# Power_Supply.net
KiCad netlist of a schematic drawn in EAGLE
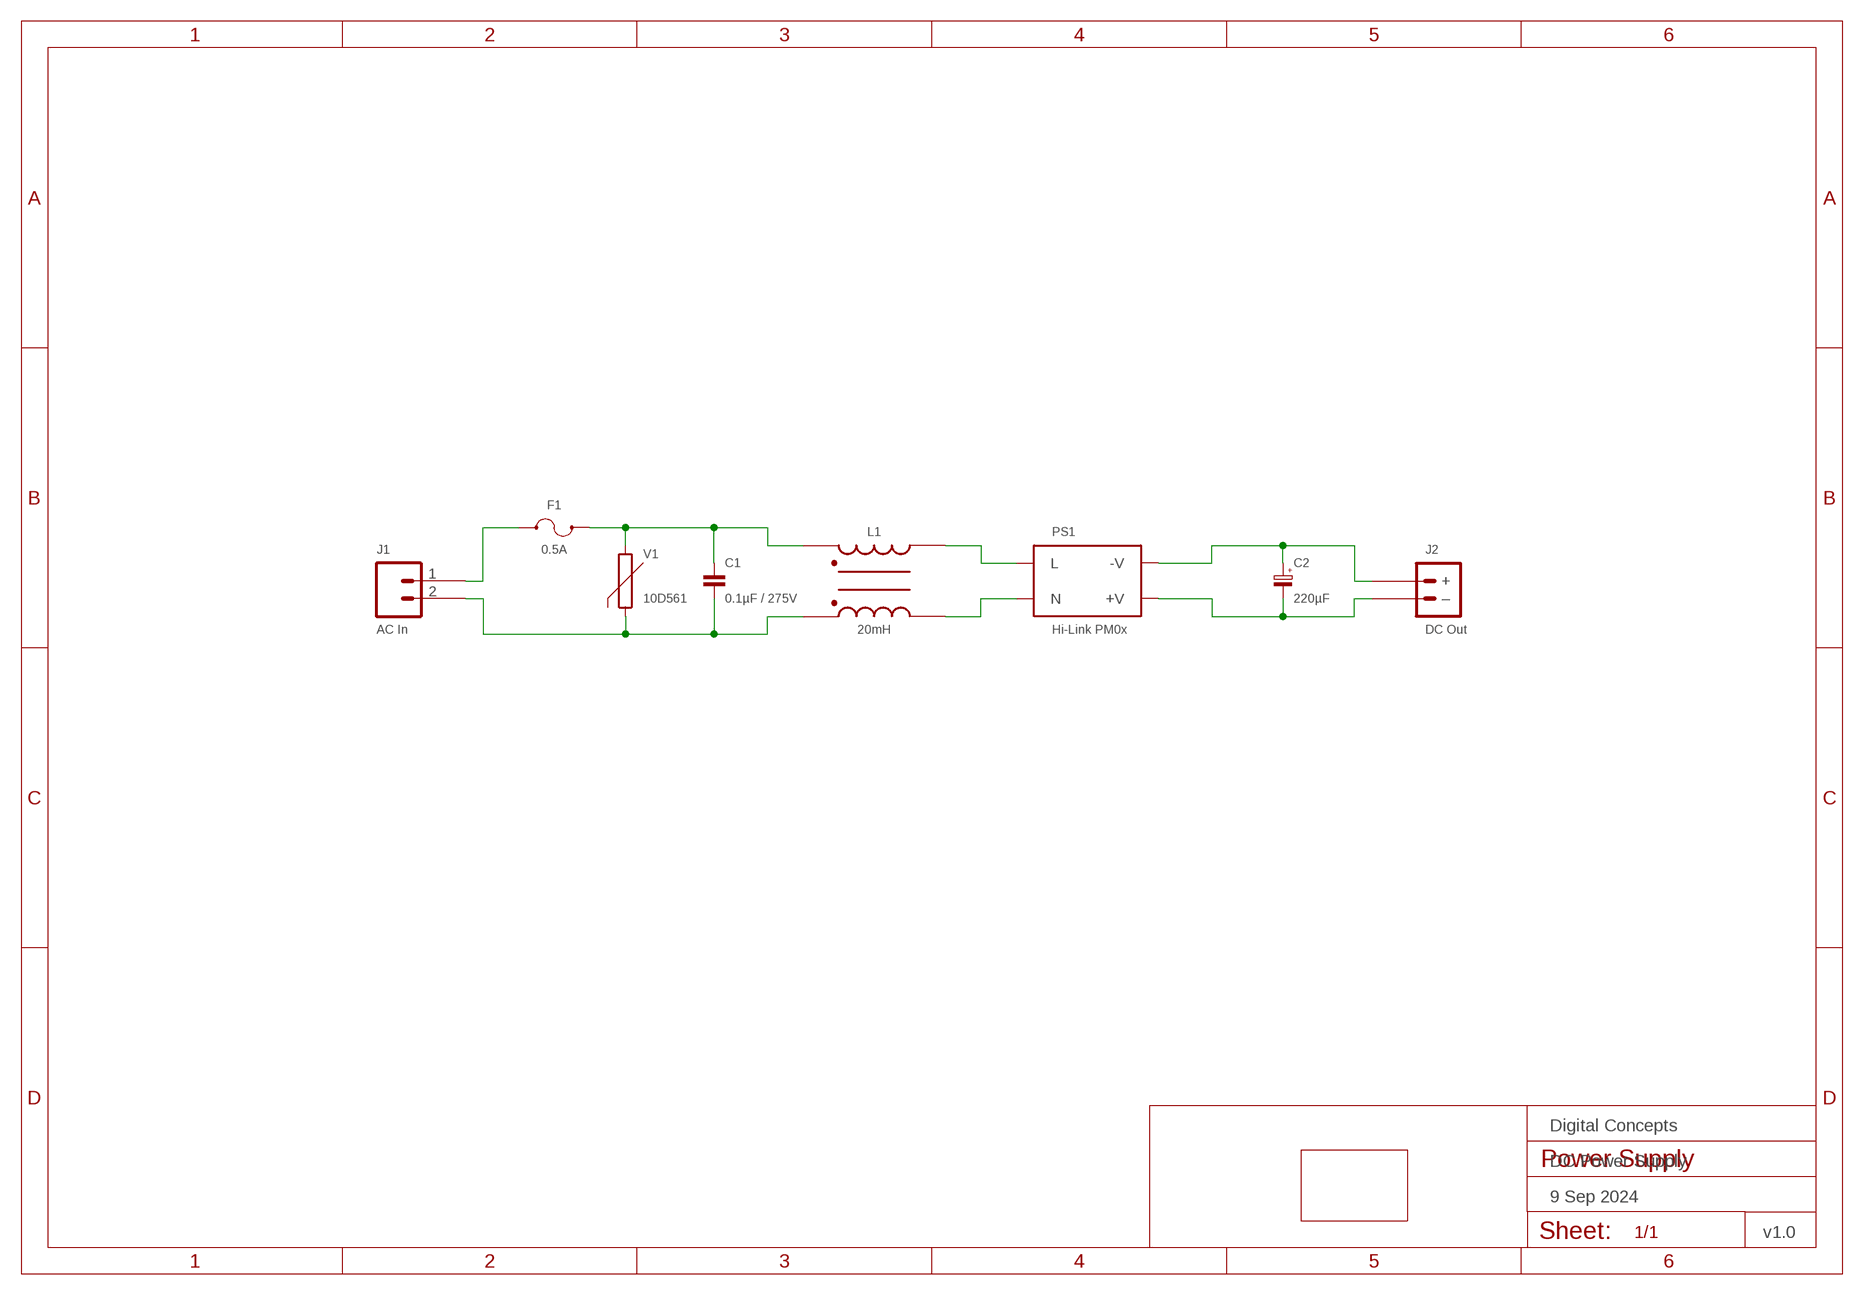
[diagram p0: schematic, sheet 1]

(export (version "E")
  (design (tool "Eeschema 10.0.6"))
  (components
    (comp (ref "C1")
      (value "0.1µF / 275V")
      (footprint "eagle-import:CAPACITOR-TENTA-SUPPRESSION")
      (libsource (lib "eagle-import") (part "CAPACITOR-TENTA-SUPPRESSION"))
    )
    (comp (ref "C2")
      (value "220µF")
      (footprint "eagle-import:E5-10,5")
      (libsource (lib "eagle-import") (part "CAPACITOR-ELECTROLYTICE5-10.5"))
    )
    (comp (ref "F1")
      (value "0.5A")
      (footprint "eagle-import:FUSE-HOLDER-1808")
      (libsource (lib "eagle-import") (part "FUSE-HOLDER-1808"))
    )
    (comp (ref "J1")
      (value "AC In")
      (footprint "eagle-import:JST-XH2.4-2-HORIZONTAL")
      (libsource (lib "eagle-import") (part "JST-XH2.54-2-HORIZONTAL"))
    )
    (comp (ref "J2")
      (value "DC Out")
      (footprint "eagle-import:JST-PH2.0-2-VERTICAL-POWER")
      (libsource (lib "eagle-import") (part "JST-PH2.0-2-VERTICAL-POWER"))
    )
    (comp (ref "L1")
      (value "20mH")
      (footprint "eagle-import:INDUCTOR-UU9.8")
      (libsource (lib "eagle-import") (part "INDUCTOR-COMMON-MODE-UU9.8"))
    )
    (comp (ref "PCB1")
      (value "PCB-OUTLINE-64X31")
      (footprint "eagle-import:PCB-POWER-SUPPLY")
      (libsource (lib "eagle-import") (part "PCB-OUTLINE-64X31"))
    )
    (comp (ref "PS1")
      (value "Hi-Link PM0x")
      (footprint "eagle-import:HI-LINK")
      (libsource (lib "eagle-import") (part "HI-LINK-POWER-SUPPLY"))
    )
    (comp (ref "V1")
      (value "10D561")
      (footprint "eagle-import:VARISTOR-10D561")
      (libsource (lib "eagle-import") (part "VARISTOR-10D561"))
    )
  )
  (nets
    (net (code "1") (name "Net-(C1-1)") (class "Default")
      (node (ref "C1") (pin "P$1") (pinfunction "1_P$1") (pintype "passive"))
      (node (ref "F1") (pin "P$2") (pinfunction "2_P$2") (pintype "passive"))
      (node (ref "L1") (pin "P$1") (pinfunction "1_P$1") (pintype "passive"))
      (node (ref "V1") (pin "2") (pinfunction "2_2") (pintype "passive"))
    )
    (net (code "2") (name "Net-(C1-2)") (class "Default")
      (node (ref "C1") (pin "P$2") (pinfunction "2_P$2") (pintype "passive"))
      (node (ref "J1") (pin "2") (pinfunction "2_2") (pintype "passive"))
      (node (ref "L1") (pin "P$4") (pinfunction "4_P$4") (pintype "passive"))
      (node (ref "V1") (pin "1") (pinfunction "1_1") (pintype "passive"))
    )
    (net (code "3") (name "Net-(F1-1)") (class "Default")
      (node (ref "F1") (pin "P$1") (pinfunction "1_P$1") (pintype "passive"))
      (node (ref "J1") (pin "1") (pinfunction "1_1") (pintype "passive"))
    )
    (net (code "4") (name "Net-(J2-–)") (class "Default")
      (node (ref "C2") (pin "-") (pinfunction "-_-") (pintype "passive"))
      (node (ref "J2") (pin "-") (pinfunction "–_-") (pintype "power_in"))
      (node (ref "PS1") (pin "+VO") (pinfunction "+V_+VO") (pintype "power_in"))
    )
    (net (code "5") (name "Net-(L1-2)") (class "Default")
      (node (ref "L1") (pin "P$2") (pinfunction "2_P$2") (pintype "passive"))
      (node (ref "PS1") (pin "AC-L") (pinfunction "L_AC-L") (pintype "power_in"))
    )
    (net (code "6") (name "Net-(L1-3)") (class "Default")
      (node (ref "L1") (pin "P$3") (pinfunction "3_P$3") (pintype "passive"))
      (node (ref "PS1") (pin "AC-N") (pinfunction "N_AC-N") (pintype "power_in"))
    )
    (net (code "7") (name "Net-(PS1--V)") (class "Default")
      (node (ref "C2") (pin "+") (pinfunction "+_+") (pintype "passive"))
      (node (ref "J2") (pin "+") (pinfunction "+_+") (pintype "power_in"))
      (node (ref "PS1") (pin "-VO") (pinfunction "-V_-VO") (pintype "power_in"))
    )
  )
)
